# LSM6DSV_MAG_JST2.net
KiCad netlist of a schematic drawn in EasyEDA Pro
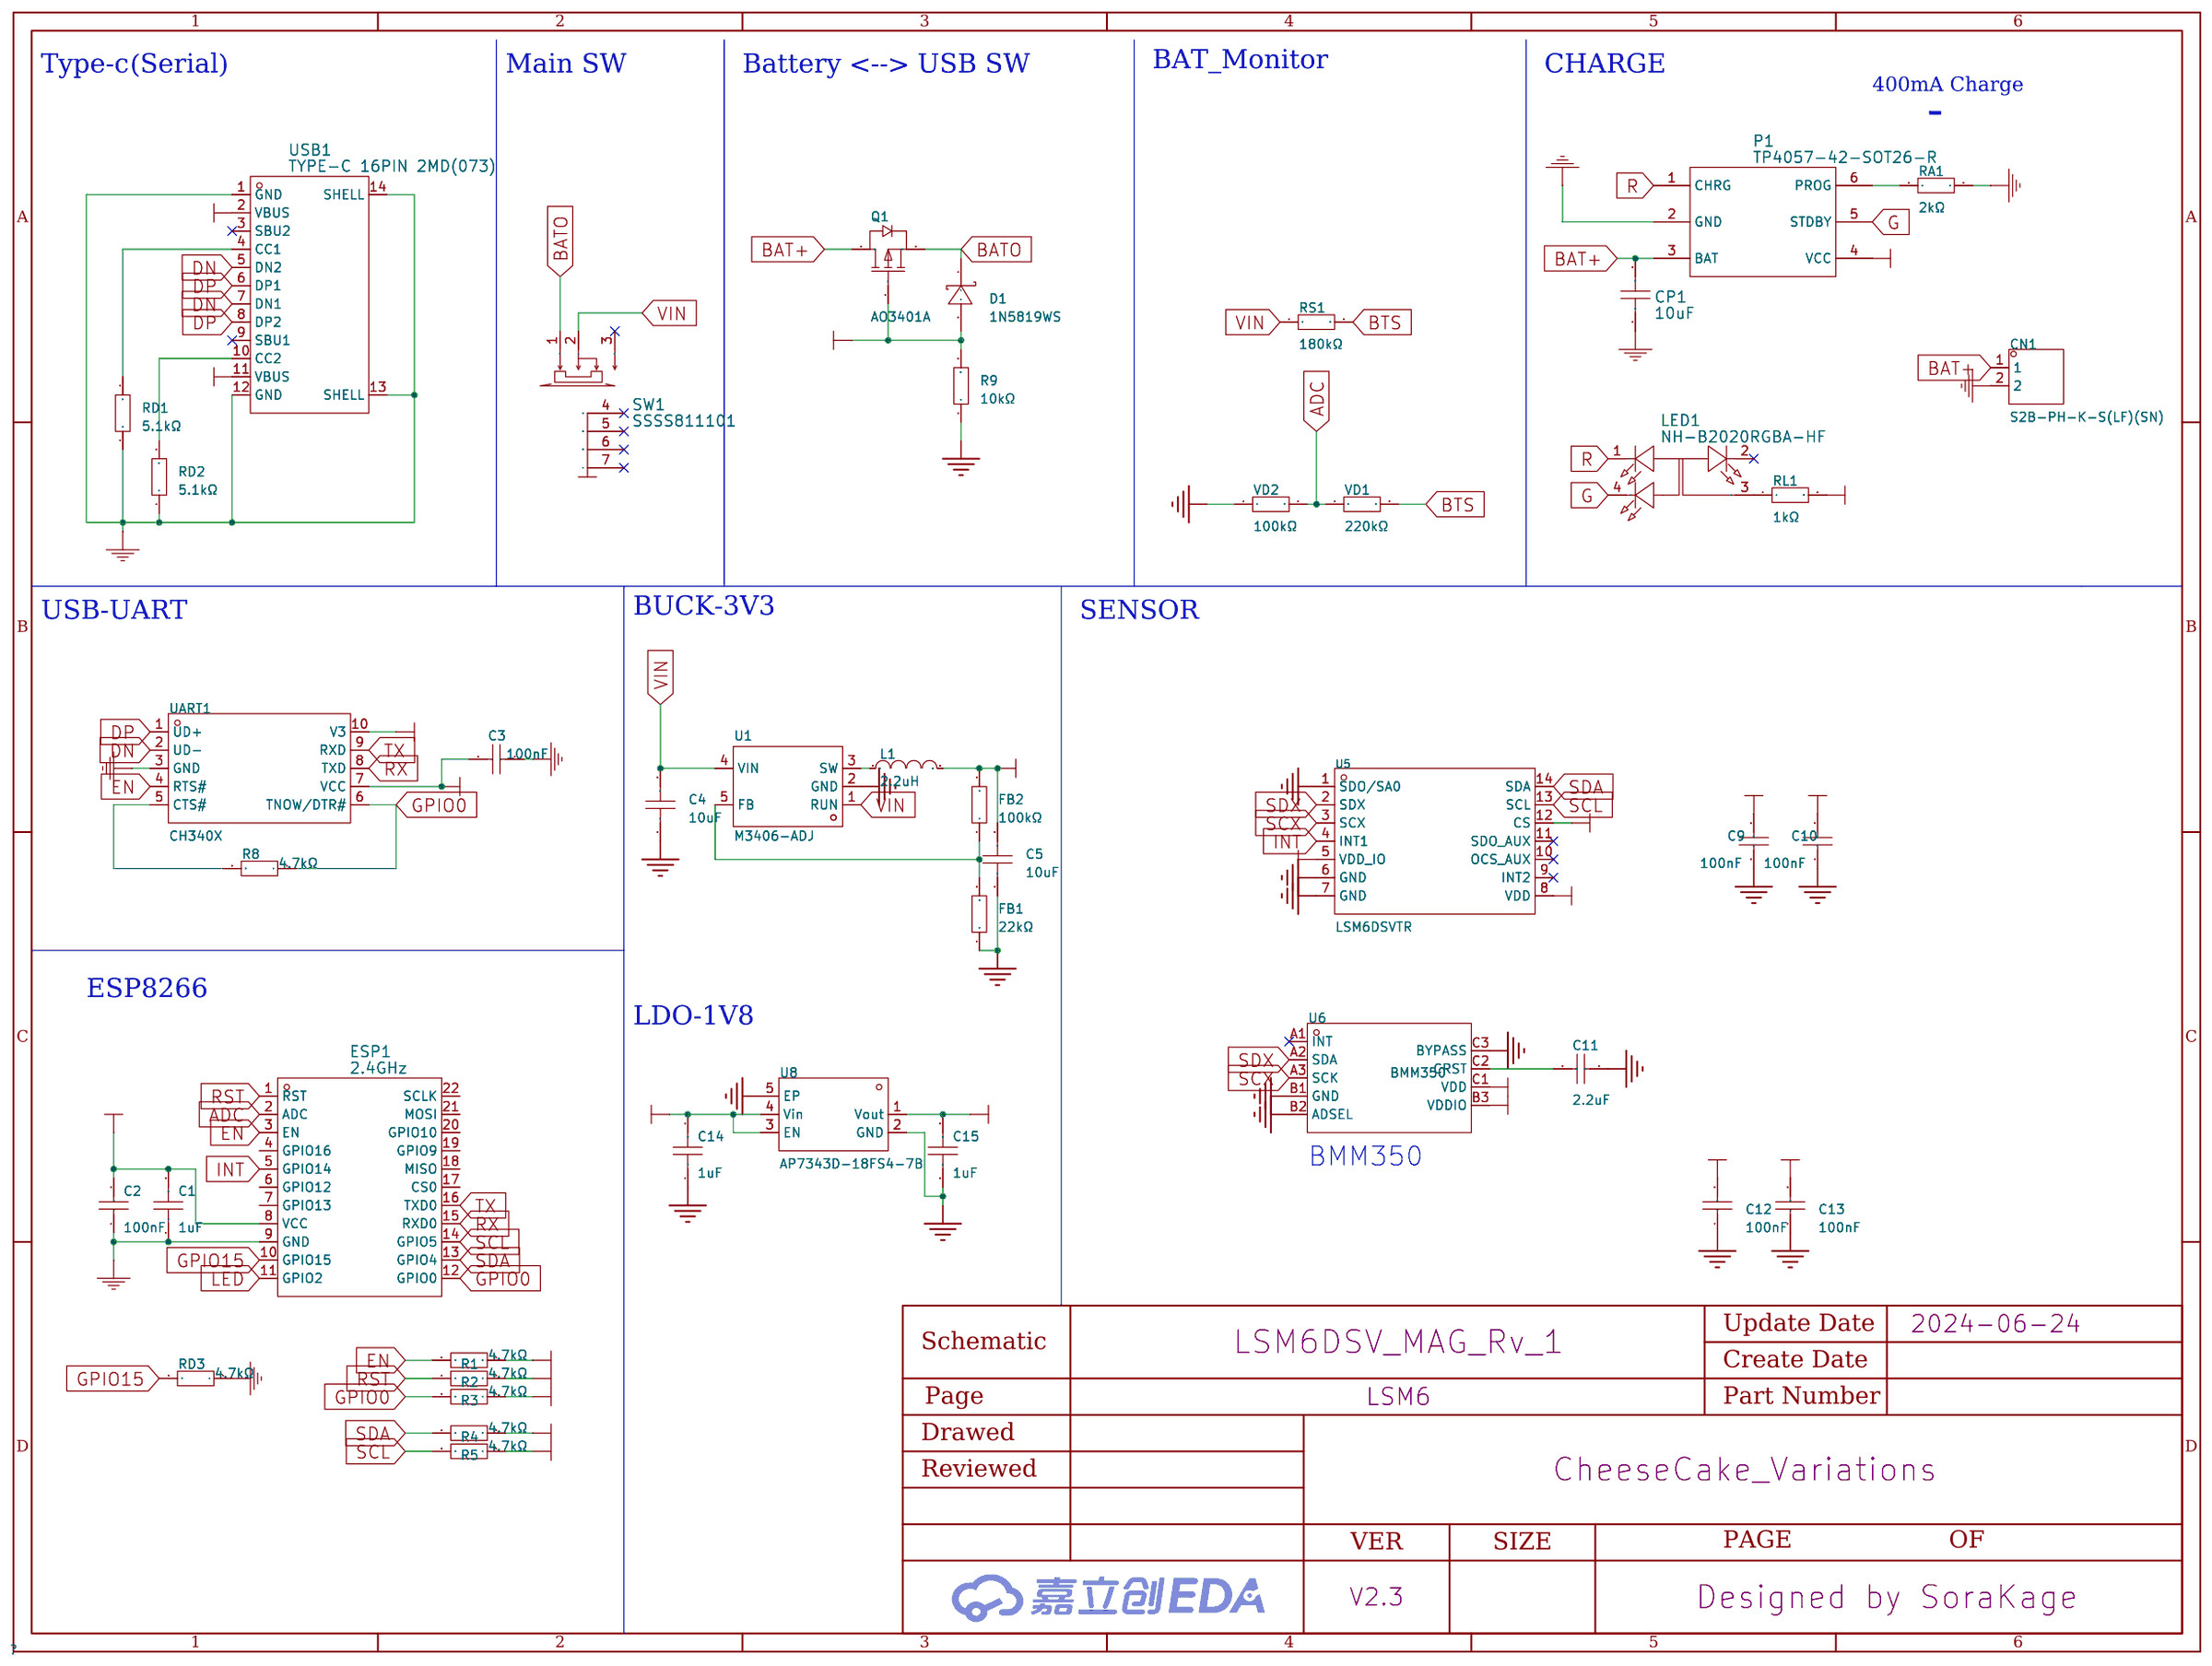
[diagram p0: schematic sheet]

(export (version "E")
  (design (tool "Eeschema 10.0.6"))
  (components
    (comp (ref "C1")
      (value "1uF")
      (footprint "easyedapro:C0402")
      (description "容值:1uF;精度:±10%;额定电压:25V;材质(温度系数):X5R;")
      (fields
        (field (name "Manufacturer Part") "CL05A105KA5NQNC")
        (field (name "Manufacturer") "SAMSUNG(三星)")
      )
      (libsource (lib "easyedapro") (part "CL05A105KA5NQNC"))
    )
    (comp (ref "C2")
      (value "100nF")
      (footprint "easyedapro:C0402")
      (description "容值:100nF;精度:±10%;额定电压:16V;材质(温度系数):X7R;")
      (fields
        (field (name "Manufacturer Part") "CL05B104KO5NNNC")
        (field (name "Manufacturer") "SAMSUNG(三星)")
      )
      (libsource (lib "easyedapro") (part "CL05B104KO5NNNC"))
    )
    (comp (ref "C3")
      (value "100nF")
      (footprint "easyedapro:C0402")
      (description "容值:100nF;精度:±10%;额定电压:16V;材质(温度系数):X7R;")
      (fields
        (field (name "Manufacturer Part") "CL05B104KO5NNNC")
        (field (name "Manufacturer") "SAMSUNG(三星)")
      )
      (libsource (lib "easyedapro") (part "CL05B104KO5NNNC"))
    )
    (comp (ref "C4")
      (value "10uF")
      (footprint "easyedapro:C0603")
      (description "容值:10uF;精度:±10%;额定电压:10V;材质(温度系数):X5R;")
      (fields
        (field (name "Manufacturer Part") "CL10A106KP8NNNC")
        (field (name "Manufacturer") "SAMSUNG(三星)")
      )
      (libsource (lib "easyedapro") (part "CL10A106KP8NNNC"))
    )
    (comp (ref "C5")
      (value "10uF")
      (footprint "easyedapro:C0603")
      (description "容值:10uF;精度:±10%;额定电压:10V;材质(温度系数):X5R;")
      (fields
        (field (name "Manufacturer Part") "CL10A106KP8NNNC")
        (field (name "Manufacturer") "SAMSUNG(三星)")
      )
      (libsource (lib "easyedapro") (part "CL10A106KP8NNNC"))
    )
    (comp (ref "C9")
      (value "100nF")
      (footprint "easyedapro:C0402")
      (description "容值:100nF;精度:±10%;额定电压:16V;材质(温度系数):X7R;")
      (fields
        (field (name "Manufacturer Part") "CL05B104KO5NNNC")
        (field (name "Manufacturer") "SAMSUNG(三星)")
      )
      (libsource (lib "easyedapro") (part "CL05B104KO5NNNC"))
    )
    (comp (ref "C10")
      (value "100nF")
      (footprint "easyedapro:C0402")
      (description "容值:100nF;精度:±10%;额定电压:16V;材质(温度系数):X7R;")
      (fields
        (field (name "Manufacturer Part") "CL05B104KO5NNNC")
        (field (name "Manufacturer") "SAMSUNG(三星)")
      )
      (libsource (lib "easyedapro") (part "CL05B104KO5NNNC"))
    )
    (comp (ref "C11")
      (value "2.2uF")
      (footprint "easyedapro:C0805")
      (description "容值:2.2uF;精度:±10%;额定电压:10V;材质(温度系数):X7R;")
      (fields
        (field (name "Manufacturer Part") "GCM21BR71A225KA37L")
        (field (name "Manufacturer") "muRata(村田)")
      )
      (libsource (lib "easyedapro") (part "GCM21BR71A225KA37L"))
    )
    (comp (ref "C12")
      (value "100nF")
      (footprint "easyedapro:C0402")
      (description "容值:100nF;精度:±10%;额定电压:16V;材质(温度系数):X7R;")
      (fields
        (field (name "Manufacturer Part") "CL05B104KO5NNNC")
        (field (name "Manufacturer") "SAMSUNG(三星)")
      )
      (libsource (lib "easyedapro") (part "CL05B104KO5NNNC"))
    )
    (comp (ref "C13")
      (value "100nF")
      (footprint "easyedapro:C0402")
      (description "容值:100nF;精度:±10%;额定电压:16V;材质(温度系数):X7R;")
      (fields
        (field (name "Manufacturer Part") "CL05B104KO5NNNC")
        (field (name "Manufacturer") "SAMSUNG(三星)")
      )
      (libsource (lib "easyedapro") (part "CL05B104KO5NNNC"))
    )
    (comp (ref "C14")
      (value "1uF")
      (footprint "easyedapro:C0402")
      (description "容值:1uF;精度:±10%;额定电压:25V;材质(温度系数):X5R;")
      (fields
        (field (name "Manufacturer Part") "CL05A105KA5NQNC")
        (field (name "Manufacturer") "SAMSUNG(三星)")
      )
      (libsource (lib "easyedapro") (part "CL05A105KA5NQNC"))
    )
    (comp (ref "C15")
      (value "1uF")
      (footprint "easyedapro:C0402")
      (description "容值:1uF;精度:±10%;额定电压:25V;材质(温度系数):X5R;")
      (fields
        (field (name "Manufacturer Part") "CL05A105KA5NQNC")
        (field (name "Manufacturer") "SAMSUNG(三星)")
      )
      (libsource (lib "easyedapro") (part "CL05A105KA5NQNC"))
    )
    (comp (ref "CN1")
      (value "S2B-PH-K-S(LF)(SN)")
      (footprint "easyedapro:CONN-TH_S2B-PH-K-S-LF-SN")
      (description "插针结构:1x2P;间距:2mm;安装方式:弯插;参考系列:PH;总PIN数:2P;排数:1;每排PIN数:2;行距:-;触头材质:黄铜;")
      (fields (field (name "Manufacturer") "JST"))
      (libsource (lib "easyedapro") (part "S2B-PH-K-S(LF)(SN)"))
    )
    (comp (ref "CP1")
      (value "10uF")
      (footprint "easyedapro:C0603")
      (fields
        (field (name "Manufacturer Part") "CL10A106KP8NNNC")
        (field (name "Manufacturer") "SAMSUNG(三星)")
      )
      (libsource (lib "easyedapro") (part "10uF"))
    )
    (comp (ref "D1")
      (value "1N5819WS")
      (footprint "easyedapro:SOD-323_L1.8-W1.3-LS2.5-RD")
      (description "直流反向耐压(Vr):40V;平均整流电流(Io):1A;正向压降(Vf):600mV@1A;")
      (fields (field (name "Manufacturer") "Hottech(合科泰)"))
      (libsource (lib "easyedapro") (part "1N5819WS"))
    )
    (comp (ref "ESP1")
      (value "2.4GHz")
      (description "核心处理器:ESP8266芯片;频率:2.4GHz;天线形式:板载PCB天线;发射功率:16dBm;接收灵敏度:-90dBm;")
      (fields
        (field (name "Manufacturer Part") "ESP-12F(ESP8266MOD)")
        (field (name "Manufacturer") "Ai-Thinker(安信可)")
      )
      (libsource (lib "easyedapro") (part "ESP-12F(ESP8266MOD)"))
    )
    (comp (ref "FB1")
      (value "22kΩ")
      (footprint "easyedapro:R0402")
      (description "电阻类型:厚膜电阻;阻值:22kΩ;精度:±1%;功率:62.5mW;")
      (fields
        (field (name "Manufacturer Part") "0402WGF2202TCE")
        (field (name "Manufacturer") "UNI-ROYAL(厚声)")
      )
      (libsource (lib "easyedapro") (part "0402WGF2202TCE"))
    )
    (comp (ref "FB2")
      (value "100kΩ")
      (footprint "easyedapro:R0402")
      (description "电阻类型:厚膜电阻;阻值:100kΩ;精度:±1%;功率:62.5mW;")
      (fields
        (field (name "Manufacturer Part") "0402WGF1003TCE")
        (field (name "Manufacturer") "UNI-ROYAL(厚声)")
      )
      (libsource (lib "easyedapro") (part "0402WGF1003TCE"))
    )
    (comp (ref "L1")
      (value "2.2uH")
      (footprint "easyedapro:IND-SMD_L2.5-W2.0_YXMBL252010P")
      (description "类型:一体成型电感;电感值:2.2uH;精度:±20%;额定电流:2.1A;饱和电流(Isat):3A;")
      (fields (field (name "Manufacturer Part") "APH252010T2R2M") (field (name "Manufacturer") "APV(爱普微)"))
      (libsource (lib "easyedapro") (part "APH252010T2R2M"))
    )
    (comp (ref "LED1")
      (value "NH-B2020RGBA-HF")
      (footprint "easyedapro:LED-ARRAY-SMD_4P-L2.1-W2.1-TL_NH-B2020RGBA")
      (fields (field (name "Manufacturer") "国星光电"))
      (libsource (lib "easyedapro") (part "NH-B2020RGBA-HF"))
    )
    (comp (ref "P1")
      (value "TP4057-42-SOT26-R")
      (footprint "easyedapro:SOT-23-6_L2.9-W1.6-P0.95-LS2.8-BL")
      (fields (field (name "Manufacturer") "TOPPOWER(南京拓微)"))
      (libsource (lib "easyedapro") (part "TP4057"))
    )
    (comp (ref "Q1")
      (value "AO3401A")
      (footprint "easyedapro:SOT-23_L2.9-W1.3-P1.90-LS2.4-BR")
      (description "类型:P沟道;漏源电压(Vdss):30V;连续漏极电流(Id):4A;功率(Pd):1.4W;导通电阻(RDS(on)@Vgs,Id):44mΩ@10V,4.3A;")
      (fields (field (name "Manufacturer") "AOS"))
      (libsource (lib "easyedapro") (part "AO3401A"))
    )
    (comp (ref "R1")
      (value "4.7kΩ")
      (footprint "easyedapro:R0402")
      (description "电阻类型:厚膜电阻;阻值:4.7kΩ;精度:±1%;功率:62.5mW;")
      (fields
        (field (name "Manufacturer Part") "0402WGF4701TCE")
        (field (name "Manufacturer") "UNI-ROYAL(厚声)")
      )
      (libsource (lib "easyedapro") (part "0402WGF4701TCE"))
    )
    (comp (ref "R2")
      (value "4.7kΩ")
      (footprint "easyedapro:R0402")
      (description "电阻类型:厚膜电阻;阻值:4.7kΩ;精度:±1%;功率:62.5mW;")
      (fields
        (field (name "Manufacturer Part") "0402WGF4701TCE")
        (field (name "Manufacturer") "UNI-ROYAL(厚声)")
      )
      (libsource (lib "easyedapro") (part "0402WGF4701TCE"))
    )
    (comp (ref "R3")
      (value "4.7kΩ")
      (footprint "easyedapro:R0402")
      (description "电阻类型:厚膜电阻;阻值:4.7kΩ;精度:±1%;功率:62.5mW;")
      (fields
        (field (name "Manufacturer Part") "0402WGF4701TCE")
        (field (name "Manufacturer") "UNI-ROYAL(厚声)")
      )
      (libsource (lib "easyedapro") (part "0402WGF4701TCE"))
    )
    (comp (ref "R4")
      (value "4.7kΩ")
      (footprint "easyedapro:R0402")
      (description "电阻类型:厚膜电阻;阻值:4.7kΩ;精度:±1%;功率:62.5mW;")
      (fields
        (field (name "Manufacturer Part") "0402WGF4701TCE")
        (field (name "Manufacturer") "UNI-ROYAL(厚声)")
      )
      (libsource (lib "easyedapro") (part "0402WGF4701TCE"))
    )
    (comp (ref "R5")
      (value "4.7kΩ")
      (footprint "easyedapro:R0402")
      (description "电阻类型:厚膜电阻;阻值:4.7kΩ;精度:±1%;功率:62.5mW;")
      (fields
        (field (name "Manufacturer Part") "0402WGF4701TCE")
        (field (name "Manufacturer") "UNI-ROYAL(厚声)")
      )
      (libsource (lib "easyedapro") (part "0402WGF4701TCE"))
    )
    (comp (ref "R8")
      (value "4.7kΩ")
      (footprint "easyedapro:R0402")
      (description "电阻类型:厚膜电阻;阻值:4.7kΩ;精度:±1%;功率:62.5mW;")
      (fields
        (field (name "Manufacturer Part") "0402WGF4701TCE")
        (field (name "Manufacturer") "UNI-ROYAL(厚声)")
      )
      (libsource (lib "easyedapro") (part "0402WGF4701TCE"))
    )
    (comp (ref "R9")
      (value "10kΩ")
      (footprint "easyedapro:R0402")
      (description "电阻类型:厚膜电阻;阻值:10kΩ;精度:±1%;功率:62.5mW;")
      (fields
        (field (name "Manufacturer Part") "0402WGF1002TCE")
        (field (name "Manufacturer") "UNI-ROYAL(厚声)")
      )
      (libsource (lib "easyedapro") (part "0402WGF1002TCE"))
    )
    (comp (ref "RA1")
      (value "2kΩ")
      (footprint "easyedapro:R0402")
      (description "电阻类型:厚膜电阻;阻值:2kΩ;精度:±1%;功率:62.5mW;")
      (fields
        (field (name "Manufacturer Part") "0402WGF2001TCE")
        (field (name "Manufacturer") "UNI-ROYAL(厚声)")
      )
      (libsource (lib "easyedapro") (part "0402WGF2001TCE"))
    )
    (comp (ref "RD1")
      (value "5.1kΩ")
      (footprint "easyedapro:R0402")
      (description "电阻类型:厚膜电阻;阻值:5.1kΩ;精度:±1%;功率:62.5mW;")
      (fields
        (field (name "Manufacturer Part") "0402WGF5101TCE")
        (field (name "Manufacturer") "UNI-ROYAL(厚声)")
      )
      (libsource (lib "easyedapro") (part "0402WGF5101TCE"))
    )
    (comp (ref "RD2")
      (value "5.1kΩ")
      (footprint "easyedapro:R0402")
      (description "电阻类型:厚膜电阻;阻值:5.1kΩ;精度:±1%;功率:62.5mW;")
      (fields
        (field (name "Manufacturer Part") "0402WGF5101TCE")
        (field (name "Manufacturer") "UNI-ROYAL(厚声)")
      )
      (libsource (lib "easyedapro") (part "0402WGF5101TCE"))
    )
    (comp (ref "RD3")
      (value "4.7kΩ")
      (footprint "easyedapro:R0402")
      (description "电阻类型:厚膜电阻;阻值:4.7kΩ;精度:±1%;功率:62.5mW;")
      (fields
        (field (name "Manufacturer Part") "0402WGF4701TCE")
        (field (name "Manufacturer") "UNI-ROYAL(厚声)")
      )
      (libsource (lib "easyedapro") (part "0402WGF4701TCE"))
    )
    (comp (ref "RL1")
      (value "1kΩ")
      (footprint "easyedapro:R0402")
      (description "电阻类型:厚膜电阻;阻值:1kΩ;精度:±1%;功率:62.5mW;")
      (fields
        (field (name "Manufacturer Part") "0402WGF1001TCE")
        (field (name "Manufacturer") "UNI-ROYAL(厚声)")
      )
      (libsource (lib "easyedapro") (part "0402WGF1001TCE"))
    )
    (comp (ref "RS1")
      (value "180kΩ")
      (footprint "easyedapro:R0402")
      (description "阻值:180kΩ;精度:±1%;功率:62.5mW;温度系数:±100ppm/°C;电阻类型:厚膜电阻;")
      (fields
        (field (name "Manufacturer Part") "0402WGF1803TCE")
        (field (name "Manufacturer") "UNI-ROYAL(厚声)")
      )
      (libsource (lib "easyedapro") (part "0402WGF1803TCE"))
    )
    (comp (ref "SW1")
      (value "SSSS811101")
      (footprint "easyedapro:SW-SMD_SSSS811101")
      (fields (field (name "Manufacturer") "ALPSALPINE(阿尔卑斯阿尔派)"))
      (libsource (lib "easyedapro") (part "SSSS811101"))
    )
    (comp (ref "U1")
      (value "M3406-ADJ")
      (footprint "easyedapro:SOT-23-5_L3.0-W1.7-P0.95-LS2.8-BR")
      (description "功能类型:降压型;同步整流:-;输出通道数:-;拓扑结构:-;输入电压:-;输出电流(最大值):-;开关频率:-;")
      (fields (field (name "Manufacturer") "西安航天民芯"))
      (libsource (lib "easyedapro") (part "M3406"))
    )
    (comp (ref "U5")
      (value "LSM6DSVTR")
      (footprint "easyedapro:LGA-14_L3.0-W2.5-P0.50-TL")
      (description "传感器类型:加速度计陀螺仪;")
      (fields (field (name "Manufacturer") "ST(意法半导体)"))
      (libsource (lib "easyedapro") (part "LSM6DSVTR"))
    )
    (comp (ref "U6")
      (value "BMM350")
      (footprint "easyedapro:WLCSP-9_L1.3-W1.3-R3-C3-P0.40-TL")
      (libsource (lib "easyedapro") (part "BMM350"))
    )
    (comp (ref "U8")
      (value "AP7343D-18FS4-7B")
      (footprint "easyedapro:X2-DFN1010-4_L1.0-W1.0-P0.65-BL-EP")
      (description "输出类型:固定;最大输入电压:5.25V;输出电压:1.8V;最大输出电流:300mA;电源纹波抑制比(PSRR):75dB@(1kHz);输出极性:正极;")
      (fields (field (name "Manufacturer") "DIODES(美台)"))
      (libsource (lib "easyedapro") (part "AP7343D-18FS4-7B"))
    )
    (comp (ref "UART1")
      (value "CH340X")
      (footprint "easyedapro:MSOP-10_L3.0-W3.0-P0.50-LS5.0-BL")
      (fields (field (name "Manufacturer") "WCH(南京沁恒)"))
      (libsource (lib "easyedapro") (part "CH340X"))
    )
    (comp (ref "USB1")
      (value "TYPE-C 16PIN 2MD(073)")
      (footprint "easyedapro:USB-C-SMD_TYPE-C-6PIN-2MD-073")
      (fields (field (name "Manufacturer") "SHOU HAN(首韩)"))
      (libsource (lib "easyedapro") (part "TYPE-C 16PIN 2MD(073)"))
    )
    (comp (ref "VD1")
      (value "220kΩ")
      (footprint "easyedapro:R0402")
      (description "电阻类型:厚膜电阻;阻值:220kΩ;精度:±1%;功率:62.5mW;")
      (fields
        (field (name "Manufacturer Part") "0402WGF2203TCE")
        (field (name "Manufacturer") "UNI-ROYAL(厚声)")
      )
      (libsource (lib "easyedapro") (part "0402WGF2203TCE"))
    )
    (comp (ref "VD2")
      (value "100kΩ")
      (footprint "easyedapro:R0402")
      (description "电阻类型:厚膜电阻;阻值:100kΩ;精度:±1%;功率:62.5mW;")
      (fields
        (field (name "Manufacturer Part") "0402WGF1003TCE")
        (field (name "Manufacturer") "UNI-ROYAL(厚声)")
      )
      (libsource (lib "easyedapro") (part "0402WGF1003TCE"))
    )
  )
  (nets
    (net (code "1") (name "+5V") (class "Default")
      (node (ref "D1") (pin "2") (pinfunction "A_2") (pintype "unspecified"))
      (node (ref "P1") (pin "4") (pinfunction "VCC_4") (pintype "unspecified"))
      (node (ref "Q1") (pin "1") (pinfunction "G_1") (pintype "input"))
      (node (ref "R9") (pin "2") (pinfunction "2_2") (pintype "input"))
      (node (ref "RL1") (pin "2") (pinfunction "2_2") (pintype "input"))
      (node (ref "USB1") (pin "11") (pinfunction "VBUS_11") (pintype "input"))
      (node (ref "USB1") (pin "2") (pinfunction "VBUS_2") (pintype "input"))
    )
    (net (code "2") (name "1V8") (class "Default")
      (node (ref "C12") (pin "2") (pinfunction "2_2") (pintype "input"))
      (node (ref "C15") (pin "2") (pinfunction "2_2") (pintype "unspecified"))
      (node (ref "U6") (pin "C1") (pinfunction "VDD_C1") (pintype "unspecified"))
      (node (ref "U8") (pin "1") (pinfunction "Vout_1") (pintype "input"))
    )
    (net (code "3") (name "3V3") (class "Default")
      (node (ref "C1") (pin "2") (pinfunction "2_2") (pintype "unspecified"))
      (node (ref "C10") (pin "1") (pinfunction "1_1") (pintype "input"))
      (node (ref "C13") (pin "2") (pinfunction "2_2") (pintype "input"))
      (node (ref "C14") (pin "2") (pinfunction "2_2") (pintype "unspecified"))
      (node (ref "C2") (pin "2") (pinfunction "2_2") (pintype "input"))
      (node (ref "C3") (pin "2") (pinfunction "2_2") (pintype "input"))
      (node (ref "C5") (pin "2") (pinfunction "2_2") (pintype "unspecified"))
      (node (ref "C9") (pin "1") (pinfunction "1_1") (pintype "input"))
      (node (ref "ESP1") (pin "8") (pinfunction "VCC_8") (pintype "input"))
      (node (ref "FB2") (pin "2") (pinfunction "2_2") (pintype "input"))
      (node (ref "L1") (pin "2") (pinfunction "2_2") (pintype "unspecified"))
      (node (ref "R1") (pin "1") (pinfunction "1_1") (pintype "input"))
      (node (ref "R2") (pin "1") (pinfunction "1_1") (pintype "input"))
      (node (ref "R3") (pin "1") (pinfunction "1_1") (pintype "input"))
      (node (ref "R4") (pin "1") (pinfunction "1_1") (pintype "input"))
      (node (ref "R5") (pin "1") (pinfunction "1_1") (pintype "input"))
      (node (ref "U5") (pin "12") (pinfunction "CS_12") (pintype "input"))
      (node (ref "U5") (pin "5") (pinfunction "VDD_IO_5") (pintype "input"))
      (node (ref "U5") (pin "8") (pinfunction "VDD_8") (pintype "input"))
      (node (ref "U6") (pin "B3") (pinfunction "VDDIO_B3") (pintype "unspecified"))
      (node (ref "U8") (pin "3") (pinfunction "EN_3") (pintype "input"))
      (node (ref "U8") (pin "4") (pinfunction "Vin_4") (pintype "input"))
      (node (ref "UART1") (pin "10") (pinfunction "V3_10") (pintype "unspecified"))
      (node (ref "UART1") (pin "7") (pinfunction "VCC_7") (pintype "unspecified"))
    )
    (net (code "4") (name "ADC") (class "Default")
      (node (ref "ESP1") (pin "2") (pinfunction "ADC_2") (pintype "input"))
      (node (ref "VD1") (pin "1") (pinfunction "1_1") (pintype "input"))
      (node (ref "VD2") (pin "2") (pinfunction "2_2") (pintype "input"))
    )
    (net (code "5") (name "BAT+") (class "Default")
      (node (ref "CN1") (pin "1") (pinfunction "1_1") (pintype "unspecified"))
      (node (ref "CP1") (pin "2") (pinfunction "2_2") (pintype "input"))
      (node (ref "P1") (pin "3") (pinfunction "BAT_3") (pintype "unspecified"))
      (node (ref "Q1") (pin "3") (pinfunction "D_3") (pintype "input"))
    )
    (net (code "6") (name "BATO") (class "Default")
      (node (ref "D1") (pin "1") (pinfunction "K_1") (pintype "unspecified"))
      (node (ref "Q1") (pin "2") (pinfunction "S_2") (pintype "input"))
      (node (ref "SW1") (pin "1") (pinfunction "1_1") (pintype "input"))
    )
    (net (code "7") (name "BTS") (class "Default")
      (node (ref "RS1") (pin "2") (pinfunction "2_2") (pintype "input"))
      (node (ref "VD1") (pin "2") (pinfunction "2_2") (pintype "input"))
    )
    (net (code "8") (name "DN") (class "Default")
      (node (ref "UART1") (pin "2") (pinfunction "UD-_2") (pintype "unspecified"))
      (node (ref "USB1") (pin "5") (pinfunction "DN2_5") (pintype "input"))
      (node (ref "USB1") (pin "7") (pinfunction "DN1_7") (pintype "input"))
    )
    (net (code "9") (name "DP") (class "Default")
      (node (ref "UART1") (pin "1") (pinfunction "UD+_1") (pintype "unspecified"))
      (node (ref "USB1") (pin "6") (pinfunction "DP1_6") (pintype "input"))
      (node (ref "USB1") (pin "8") (pinfunction "DP2_8") (pintype "input"))
    )
    (net (code "10") (name "EN") (class "Default")
      (node (ref "ESP1") (pin "3") (pinfunction "EN_3") (pintype "input"))
      (node (ref "R1") (pin "2") (pinfunction "2_2") (pintype "input"))
      (node (ref "UART1") (pin "4") (pinfunction "RTS#_4") (pintype "unspecified"))
    )
    (net (code "11") (name "G") (class "Default")
      (node (ref "LED1") (pin "4") (pinfunction "-_4") (pintype "input"))
      (node (ref "P1") (pin "5") (pinfunction "STDBY_5") (pintype "unspecified"))
    )
    (net (code "12") (name "GND") (class "Default")
      (node (ref "C1") (pin "1") (pinfunction "1_1") (pintype "unspecified"))
      (node (ref "C10") (pin "2") (pinfunction "2_2") (pintype "input"))
      (node (ref "C11") (pin "2") (pinfunction "2_2") (pintype "input"))
      (node (ref "C12") (pin "1") (pinfunction "1_1") (pintype "input"))
      (node (ref "C13") (pin "1") (pinfunction "1_1") (pintype "input"))
      (node (ref "C14") (pin "1") (pinfunction "1_1") (pintype "unspecified"))
      (node (ref "C15") (pin "1") (pinfunction "1_1") (pintype "unspecified"))
      (node (ref "C2") (pin "1") (pinfunction "1_1") (pintype "input"))
      (node (ref "C3") (pin "1") (pinfunction "1_1") (pintype "input"))
      (node (ref "C4") (pin "1") (pinfunction "1_1") (pintype "unspecified"))
      (node (ref "C5") (pin "1") (pinfunction "1_1") (pintype "unspecified"))
      (node (ref "C9") (pin "2") (pinfunction "2_2") (pintype "input"))
      (node (ref "CN1") (pin "2") (pinfunction "2_2") (pintype "unspecified"))
      (node (ref "CP1") (pin "1") (pinfunction "1_1") (pintype "input"))
      (node (ref "ESP1") (pin "9") (pinfunction "GND_9") (pintype "input"))
      (node (ref "FB1") (pin "1") (pinfunction "1_1") (pintype "input"))
      (node (ref "P1") (pin "2") (pinfunction "GND_2") (pintype "unspecified"))
      (node (ref "R9") (pin "1") (pinfunction "1_1") (pintype "input"))
      (node (ref "RA1") (pin "2") (pinfunction "2_2") (pintype "input"))
      (node (ref "RD1") (pin "1") (pinfunction "1_1") (pintype "input"))
      (node (ref "RD2") (pin "1") (pinfunction "1_1") (pintype "input"))
      (node (ref "RD3") (pin "1") (pinfunction "1_1") (pintype "input"))
      (node (ref "U1") (pin "2") (pinfunction "GND_2") (pintype "input"))
      (node (ref "U5") (pin "1") (pinfunction "SDO/SA0_1") (pintype "input"))
      (node (ref "U5") (pin "6") (pinfunction "GND_6") (pintype "input"))
      (node (ref "U5") (pin "7") (pinfunction "GND_7") (pintype "input"))
      (node (ref "U6") (pin "B1") (pinfunction "GND_B1") (pintype "unspecified"))
      (node (ref "U6") (pin "B2") (pinfunction "ADSEL_B2") (pintype "unspecified"))
      (node (ref "U6") (pin "C3") (pinfunction "BYPASS_C3") (pintype "unspecified"))
      (node (ref "U8") (pin "2") (pinfunction "GND_2") (pintype "input"))
      (node (ref "U8") (pin "5") (pinfunction "EP_5") (pintype "input"))
      (node (ref "UART1") (pin "3") (pinfunction "GND_3") (pintype "unspecified"))
      (node (ref "USB1") (pin "1") (pinfunction "GND_1") (pintype "input"))
      (node (ref "USB1") (pin "12") (pinfunction "GND_12") (pintype "input"))
      (node (ref "USB1") (pin "13") (pinfunction "SHELL_13") (pintype "input"))
      (node (ref "USB1") (pin "14") (pinfunction "SHELL_14") (pintype "input"))
      (node (ref "VD2") (pin "1") (pinfunction "1_1") (pintype "input"))
    )
    (net (code "13") (name "GPIO0") (class "Default")
      (node (ref "ESP1") (pin "12") (pinfunction "GPIO0_12") (pintype "input"))
      (node (ref "R3") (pin "2") (pinfunction "2_2") (pintype "input"))
      (node (ref "R8") (pin "1") (pinfunction "1_1") (pintype "input"))
      (node (ref "UART1") (pin "6") (pinfunction "TNOW/DTR#_6") (pintype "unspecified"))
    )
    (net (code "14") (name "GPIO15") (class "Default")
      (node (ref "ESP1") (pin "10") (pinfunction "GPIO15_10") (pintype "input"))
      (node (ref "RD3") (pin "2") (pinfunction "2_2") (pintype "input"))
    )
    (net (code "15") (name "INT") (class "Default")
      (node (ref "ESP1") (pin "5") (pinfunction "GPIO14_5") (pintype "input"))
      (node (ref "U5") (pin "4") (pinfunction "INT1_4") (pintype "input"))
    )
    (net (code "16") (name "LED") (class "Default")
      (node (ref "ESP1") (pin "11") (pinfunction "GPIO2_11") (pintype "input"))
    )
    (net (code "17") (name "Net-(LED1-+)") (class "Default")
      (node (ref "LED1") (pin "3") (pinfunction "+_3") (pintype "input"))
      (node (ref "RL1") (pin "1") (pinfunction "1_1") (pintype "input"))
    )
    (net (code "18") (name "Net-(P1-PROG)") (class "Default")
      (node (ref "P1") (pin "6") (pinfunction "PROG_6") (pintype "unspecified"))
      (node (ref "RA1") (pin "1") (pinfunction "1_1") (pintype "input"))
    )
    (net (code "19") (name "Net-(U1-FB)") (class "Default")
      (node (ref "FB1") (pin "2") (pinfunction "2_2") (pintype "input"))
      (node (ref "FB2") (pin "1") (pinfunction "1_1") (pintype "input"))
      (node (ref "U1") (pin "5") (pinfunction "FB_5") (pintype "input"))
    )
    (net (code "20") (name "Net-(U1-SW)") (class "Default")
      (node (ref "L1") (pin "1") (pinfunction "1_1") (pintype "unspecified"))
      (node (ref "U1") (pin "3") (pinfunction "SW_3") (pintype "input"))
    )
    (net (code "21") (name "Net-(U6-CRST)") (class "Default")
      (node (ref "C11") (pin "1") (pinfunction "1_1") (pintype "input"))
      (node (ref "U6") (pin "C2") (pinfunction "CRST_C2") (pintype "unspecified"))
    )
    (net (code "22") (name "Net-(UART1-CTS#)") (class "Default")
      (node (ref "R8") (pin "2") (pinfunction "2_2") (pintype "input"))
      (node (ref "UART1") (pin "5") (pinfunction "CTS#_5") (pintype "unspecified"))
    )
    (net (code "23") (name "Net-(USB1-CC1)") (class "Default")
      (node (ref "RD1") (pin "2") (pinfunction "2_2") (pintype "input"))
      (node (ref "USB1") (pin "4") (pinfunction "CC1_4") (pintype "input"))
    )
    (net (code "24") (name "Net-(USB1-CC2)") (class "Default")
      (node (ref "RD2") (pin "2") (pinfunction "2_2") (pintype "input"))
      (node (ref "USB1") (pin "10") (pinfunction "CC2_10") (pintype "input"))
    )
    (net (code "25") (name "R") (class "Default")
      (node (ref "LED1") (pin "1") (pinfunction "-_1") (pintype "input"))
      (node (ref "P1") (pin "1") (pinfunction "CHRG_1") (pintype "unspecified"))
    )
    (net (code "26") (name "RST") (class "Default")
      (node (ref "ESP1") (pin "1") (pinfunction "RST_1") (pintype "input"))
      (node (ref "R2") (pin "2") (pinfunction "2_2") (pintype "input"))
    )
    (net (code "27") (name "RX") (class "Default")
      (node (ref "ESP1") (pin "15") (pinfunction "RXD0_15") (pintype "input"))
      (node (ref "UART1") (pin "8") (pinfunction "TXD_8") (pintype "unspecified"))
    )
    (net (code "28") (name "SCL") (class "Default")
      (node (ref "ESP1") (pin "14") (pinfunction "GPIO5_14") (pintype "input"))
      (node (ref "R5") (pin "2") (pinfunction "2_2") (pintype "input"))
      (node (ref "U5") (pin "13") (pinfunction "SCL_13") (pintype "input"))
    )
    (net (code "29") (name "SCX") (class "Default")
      (node (ref "U5") (pin "3") (pinfunction "SCX_3") (pintype "input"))
      (node (ref "U6") (pin "A3") (pinfunction "SCK_A3") (pintype "unspecified"))
    )
    (net (code "30") (name "SDA") (class "Default")
      (node (ref "ESP1") (pin "13") (pinfunction "GPIO4_13") (pintype "input"))
      (node (ref "R4") (pin "2") (pinfunction "2_2") (pintype "input"))
      (node (ref "U5") (pin "14") (pinfunction "SDA_14") (pintype "input"))
    )
    (net (code "31") (name "SDX") (class "Default")
      (node (ref "U5") (pin "2") (pinfunction "SDX_2") (pintype "input"))
      (node (ref "U6") (pin "A2") (pinfunction "SDA_A2") (pintype "unspecified"))
    )
    (net (code "32") (name "TX") (class "Default")
      (node (ref "ESP1") (pin "16") (pinfunction "TXD0_16") (pintype "input"))
      (node (ref "UART1") (pin "9") (pinfunction "RXD_9") (pintype "unspecified"))
    )
    (net (code "33") (name "VIN") (class "Default")
      (node (ref "C4") (pin "2") (pinfunction "2_2") (pintype "unspecified"))
      (node (ref "RS1") (pin "1") (pinfunction "1_1") (pintype "input"))
      (node (ref "SW1") (pin "2") (pinfunction "2_2") (pintype "input"))
      (node (ref "U1") (pin "1") (pinfunction "RUN_1") (pintype "input"))
      (node (ref "U1") (pin "4") (pinfunction "VIN_4") (pintype "input"))
    )
    (net (code "34") (name "unconnected-(ESP1-CS0-Pad17)") (class "Default")
      (node (ref "ESP1") (pin "17") (pinfunction "CS0_17") (pintype "input"))
    )
    (net (code "35") (name "unconnected-(ESP1-GPIO9-Pad19)") (class "Default")
      (node (ref "ESP1") (pin "19") (pinfunction "GPIO9_19") (pintype "input"))
    )
    (net (code "36") (name "unconnected-(ESP1-GPIO10-Pad20)") (class "Default")
      (node (ref "ESP1") (pin "20") (pinfunction "GPIO10_20") (pintype "input"))
    )
    (net (code "37") (name "unconnected-(ESP1-GPIO12-Pad6)") (class "Default")
      (node (ref "ESP1") (pin "6") (pinfunction "GPIO12_6") (pintype "input"))
    )
    (net (code "38") (name "unconnected-(ESP1-GPIO13-Pad7)") (class "Default")
      (node (ref "ESP1") (pin "7") (pinfunction "GPIO13_7") (pintype "input"))
    )
    (net (code "39") (name "unconnected-(ESP1-GPIO16-Pad4)") (class "Default")
      (node (ref "ESP1") (pin "4") (pinfunction "GPIO16_4") (pintype "input"))
    )
    (net (code "40") (name "unconnected-(ESP1-MISO-Pad18)") (class "Default")
      (node (ref "ESP1") (pin "18") (pinfunction "MISO_18") (pintype "input"))
    )
    (net (code "41") (name "unconnected-(ESP1-MOSI-Pad21)") (class "Default")
      (node (ref "ESP1") (pin "21") (pinfunction "MOSI_21") (pintype "input"))
    )
    (net (code "42") (name "unconnected-(ESP1-SCLK-Pad22)") (class "Default")
      (node (ref "ESP1") (pin "22") (pinfunction "SCLK_22") (pintype "input"))
    )
    (net (code "43") (name "unconnected-(LED1---Pad2)") (class "Default")
      (node (ref "LED1") (pin "2") (pinfunction "-_2") (pintype "input+no_connect"))
    )
    (net (code "44") (name "unconnected-(SW1-Pad3)") (class "Default")
      (node (ref "SW1") (pin "3") (pinfunction "3_3") (pintype "input+no_connect"))
    )
    (net (code "45") (name "unconnected-(SW1-Pad4)") (class "Default")
      (node (ref "SW1") (pin "4") (pinfunction "4_4") (pintype "input+no_connect"))
    )
    (net (code "46") (name "unconnected-(SW1-Pad5)") (class "Default")
      (node (ref "SW1") (pin "5") (pinfunction "5_5") (pintype "input+no_connect"))
    )
    (net (code "47") (name "unconnected-(SW1-Pad6)") (class "Default")
      (node (ref "SW1") (pin "6") (pinfunction "6_6") (pintype "input+no_connect"))
    )
    (net (code "48") (name "unconnected-(SW1-Pad7)") (class "Default")
      (node (ref "SW1") (pin "7") (pinfunction "7_7") (pintype "input+no_connect"))
    )
    (net (code "49") (name "unconnected-(U5-INT2-Pad9)") (class "Default")
      (node (ref "U5") (pin "9") (pinfunction "INT2_9") (pintype "input+no_connect"))
    )
    (net (code "50") (name "unconnected-(U5-OCS_AUX-Pad10)") (class "Default")
      (node (ref "U5") (pin "10") (pinfunction "OCS_AUX_10") (pintype "input+no_connect"))
    )
    (net (code "51") (name "unconnected-(U5-SDO_AUX-Pad11)") (class "Default")
      (node (ref "U5") (pin "11") (pinfunction "SDO_AUX_11") (pintype "input+no_connect"))
    )
    (net (code "52") (name "unconnected-(U6-INT-PadA1)") (class "Default")
      (node (ref "U6") (pin "A1") (pinfunction "INT_A1") (pintype "unspecified+no_connect"))
    )
    (net (code "53") (name "unconnected-(USB1-SBU1-Pad9)") (class "Default")
      (node (ref "USB1") (pin "9") (pinfunction "SBU1_9") (pintype "input+no_connect"))
    )
    (net (code "54") (name "unconnected-(USB1-SBU2-Pad3)") (class "Default")
      (node (ref "USB1") (pin "3") (pinfunction "SBU2_3") (pintype "input+no_connect"))
    )
  )
)
